# TTGO_shield_revE.net
KiCad netlist of a schematic drawn in EAGLE
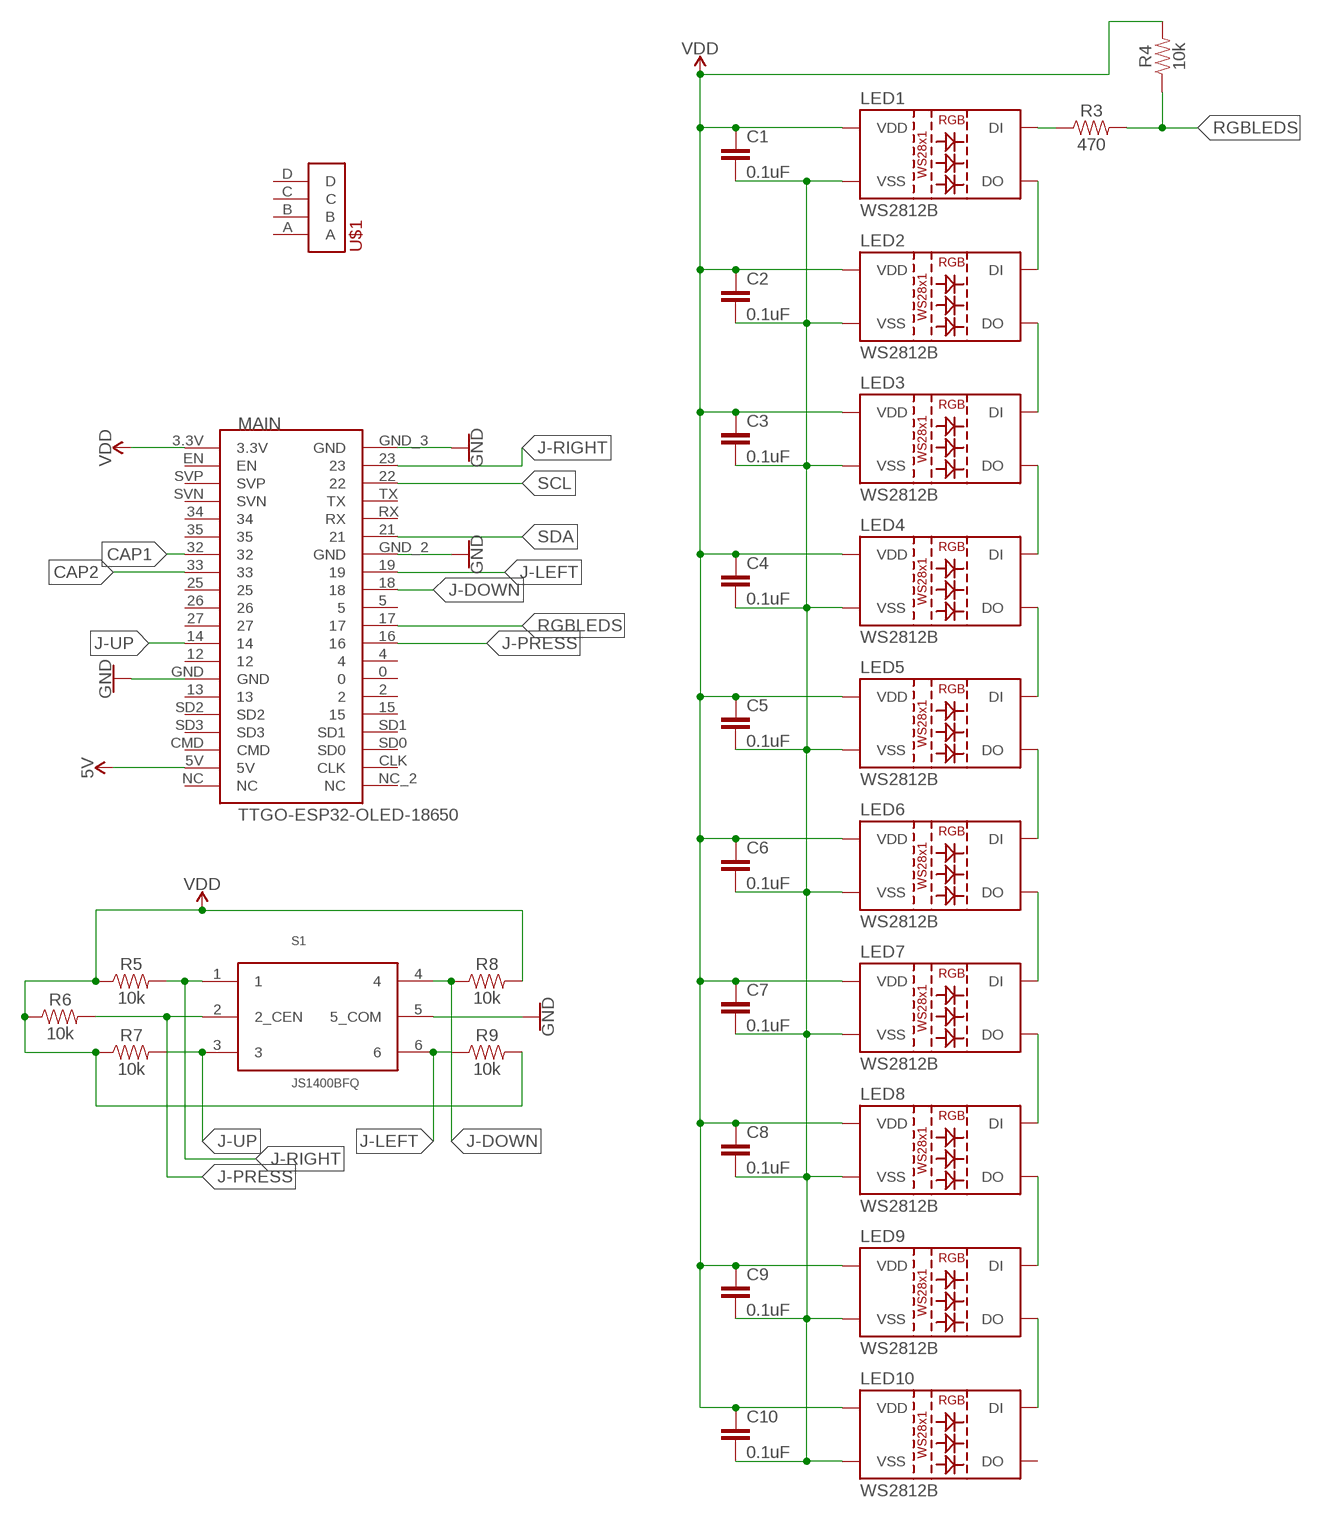
[diagram p0: schematic, sheet 1]

(export (version "E")
  (design (tool "Eeschema 10.0.6"))
  (components
    (comp (ref "C1")
      (value "0.1uF")
      (footprint "eagle-import:0603")
      (libsource (lib "eagle-import") (part "0.1UF-0603-25V-5%"))
    )
    (comp (ref "C2")
      (value "0.1uF")
      (footprint "eagle-import:0603")
      (libsource (lib "eagle-import") (part "0.1UF-0603-25V-5%"))
    )
    (comp (ref "C3")
      (value "0.1uF")
      (footprint "eagle-import:0603")
      (libsource (lib "eagle-import") (part "0.1UF-0603-25V-5%"))
    )
    (comp (ref "C4")
      (value "0.1uF")
      (footprint "eagle-import:0603")
      (libsource (lib "eagle-import") (part "0.1UF-0603-25V-5%"))
    )
    (comp (ref "C5")
      (value "0.1uF")
      (footprint "eagle-import:0603")
      (libsource (lib "eagle-import") (part "0.1UF-0603-25V-5%"))
    )
    (comp (ref "C6")
      (value "0.1uF")
      (footprint "eagle-import:0603")
      (libsource (lib "eagle-import") (part "0.1UF-0603-25V-5%"))
    )
    (comp (ref "C7")
      (value "0.1uF")
      (footprint "eagle-import:0603")
      (libsource (lib "eagle-import") (part "0.1UF-0603-25V-5%"))
    )
    (comp (ref "C8")
      (value "0.1uF")
      (footprint "eagle-import:0603")
      (libsource (lib "eagle-import") (part "0.1UF-0603-25V-5%"))
    )
    (comp (ref "C9")
      (value "0.1uF")
      (footprint "eagle-import:0603")
      (libsource (lib "eagle-import") (part "0.1UF-0603-25V-5%"))
    )
    (comp (ref "C10")
      (value "0.1uF")
      (footprint "eagle-import:0603")
      (libsource (lib "eagle-import") (part "0.1UF-0603-25V-5%"))
    )
    (comp (ref "LED1")
      (value "WS2812B")
      (footprint "eagle-import:WS2812B")
      (libsource (lib "eagle-import") (part "WS2812B"))
    )
    (comp (ref "LED2")
      (value "WS2812B")
      (footprint "eagle-import:WS2812B")
      (libsource (lib "eagle-import") (part "WS2812B"))
    )
    (comp (ref "LED3")
      (value "WS2812B")
      (footprint "eagle-import:WS2812B")
      (libsource (lib "eagle-import") (part "WS2812B"))
    )
    (comp (ref "LED4")
      (value "WS2812B")
      (footprint "eagle-import:WS2812B")
      (libsource (lib "eagle-import") (part "WS2812B"))
    )
    (comp (ref "LED5")
      (value "WS2812B")
      (footprint "eagle-import:WS2812B")
      (libsource (lib "eagle-import") (part "WS2812B"))
    )
    (comp (ref "LED6")
      (value "WS2812B")
      (footprint "eagle-import:WS2812B")
      (libsource (lib "eagle-import") (part "WS2812B"))
    )
    (comp (ref "LED7")
      (value "WS2812B")
      (footprint "eagle-import:WS2812B")
      (libsource (lib "eagle-import") (part "WS2812B"))
    )
    (comp (ref "LED8")
      (value "WS2812B")
      (footprint "eagle-import:WS2812B")
      (libsource (lib "eagle-import") (part "WS2812B"))
    )
    (comp (ref "LED9")
      (value "WS2812B")
      (footprint "eagle-import:WS2812B")
      (libsource (lib "eagle-import") (part "WS2812B"))
    )
    (comp (ref "LED10")
      (value "WS2812B")
      (footprint "eagle-import:WS2812B")
      (libsource (lib "eagle-import") (part "WS2812B"))
    )
    (comp (ref "MAIN")
      (value "TTGO-ESP32-OLED-18650")
      (footprint "eagle-import:TTGO-ESP32-OLED-18650")
      (libsource (lib "eagle-import") (part "TTGO-ESP32-OLED-18650"))
    )
    (comp (ref "R3")
      (value "470")
      (footprint "eagle-import:0603")
      (libsource (lib "eagle-import") (part "470OHM-0603-1/10W-1%"))
    )
    (comp (ref "R4")
      (value "10k")
      (footprint "eagle-import:0603")
      (libsource (lib "eagle-import") (part "10KOHM-0603-1/10W-1%"))
    )
    (comp (ref "R5")
      (value "10k")
      (footprint "eagle-import:0603")
      (libsource (lib "eagle-import") (part "10KOHM-0603-1/10W-1%"))
    )
    (comp (ref "R6")
      (value "10k")
      (footprint "eagle-import:0603")
      (libsource (lib "eagle-import") (part "10KOHM-0603-1/10W-1%"))
    )
    (comp (ref "R7")
      (value "10k")
      (footprint "eagle-import:0603")
      (libsource (lib "eagle-import") (part "10KOHM-0603-1/10W-1%"))
    )
    (comp (ref "R8")
      (value "10k")
      (footprint "eagle-import:0603")
      (libsource (lib "eagle-import") (part "10KOHM-0603-1/10W-1%"))
    )
    (comp (ref "R9")
      (value "10k")
      (footprint "eagle-import:0603")
      (libsource (lib "eagle-import") (part "10KOHM-0603-1/10W-1%"))
    )
    (comp (ref "S1")
      (value "JS1400BFQ")
      (footprint "eagle-import:JS1400BFQ")
      (libsource (lib "eagle-import") (part "JS1400BFQ"))
    )
    (comp (ref "U$1")
      (value "10120045-400LF")
      (footprint "eagle-import:10120045-400LF")
      (libsource (lib "eagle-import") (part "10120045-400LF"))
    )
  )
  (nets
    (net (code "1") (name "5V") (class "Default")
      (node (ref "MAIN") (pin "5V") (pinfunction "5V_5V") (pintype "bidirectional"))
    )
    (net (code "2") (name "CAP1") (class "Default")
      (node (ref "MAIN") (pin "32") (pinfunction "32_32") (pintype "bidirectional"))
    )
    (net (code "3") (name "CAP2") (class "Default")
      (node (ref "MAIN") (pin "33") (pinfunction "33_33") (pintype "bidirectional"))
    )
    (net (code "4") (name "GND") (class "Default")
      (node (ref "MAIN") (pin "GND") (pinfunction "GND_GND") (pintype "bidirectional"))
      (node (ref "MAIN") (pin "GND_2") (pinfunction "GND_GND_2") (pintype "bidirectional"))
      (node (ref "MAIN") (pin "GND_3") (pinfunction "GND_GND_3") (pintype "bidirectional"))
      (node (ref "S1") (pin "5") (pinfunction "5_COM_5") (pintype "bidirectional"))
    )
    (net (code "5") (name "J-DOWN") (class "Default")
      (node (ref "MAIN") (pin "18") (pinfunction "18_18") (pintype "bidirectional"))
      (node (ref "R8") (pin "1") (pinfunction "1_1") (pintype "passive"))
      (node (ref "S1") (pin "4") (pinfunction "4_4") (pintype "bidirectional"))
    )
    (net (code "6") (name "J-LEFT") (class "Default")
      (node (ref "MAIN") (pin "19") (pinfunction "19_19") (pintype "bidirectional"))
      (node (ref "R9") (pin "1") (pinfunction "1_1") (pintype "passive"))
      (node (ref "S1") (pin "6") (pinfunction "6_6") (pintype "bidirectional"))
    )
    (net (code "7") (name "J-PRESS") (class "Default")
      (node (ref "MAIN") (pin "16") (pinfunction "16_16") (pintype "bidirectional"))
      (node (ref "R6") (pin "2") (pinfunction "2_2") (pintype "passive"))
      (node (ref "S1") (pin "2") (pinfunction "2_CEN_2") (pintype "bidirectional"))
    )
    (net (code "8") (name "J-RIGHT") (class "Default")
      (node (ref "MAIN") (pin "23") (pinfunction "23_23") (pintype "bidirectional"))
      (node (ref "R5") (pin "2") (pinfunction "2_2") (pintype "passive"))
      (node (ref "S1") (pin "1") (pinfunction "1_1") (pintype "bidirectional"))
    )
    (net (code "9") (name "J-UP") (class "Default")
      (node (ref "MAIN") (pin "14") (pinfunction "14_14") (pintype "bidirectional"))
      (node (ref "R7") (pin "2") (pinfunction "2_2") (pintype "passive"))
      (node (ref "S1") (pin "3") (pinfunction "3_3") (pintype "bidirectional"))
    )
    (net (code "10") (name "Net-(LED1-DI)") (class "Default")
      (node (ref "LED1") (pin "4") (pinfunction "DI_4") (pintype "bidirectional"))
      (node (ref "R3") (pin "1") (pinfunction "1_1") (pintype "passive"))
    )
    (net (code "11") (name "Net-(LED1-DO)") (class "Default")
      (node (ref "LED1") (pin "2") (pinfunction "DO_2") (pintype "bidirectional"))
      (node (ref "LED2") (pin "4") (pinfunction "DI_4") (pintype "bidirectional"))
    )
    (net (code "12") (name "Net-(LED1-VSS)") (class "Default")
      (node (ref "C1") (pin "2") (pinfunction "2_2") (pintype "passive"))
      (node (ref "C10") (pin "2") (pinfunction "2_2") (pintype "passive"))
      (node (ref "C2") (pin "2") (pinfunction "2_2") (pintype "passive"))
      (node (ref "C3") (pin "2") (pinfunction "2_2") (pintype "passive"))
      (node (ref "C4") (pin "2") (pinfunction "2_2") (pintype "passive"))
      (node (ref "C5") (pin "2") (pinfunction "2_2") (pintype "passive"))
      (node (ref "C6") (pin "2") (pinfunction "2_2") (pintype "passive"))
      (node (ref "C7") (pin "2") (pinfunction "2_2") (pintype "passive"))
      (node (ref "C8") (pin "2") (pinfunction "2_2") (pintype "passive"))
      (node (ref "C9") (pin "2") (pinfunction "2_2") (pintype "passive"))
      (node (ref "LED1") (pin "3") (pinfunction "VSS_3") (pintype "bidirectional"))
      (node (ref "LED10") (pin "3") (pinfunction "VSS_3") (pintype "bidirectional"))
      (node (ref "LED2") (pin "3") (pinfunction "VSS_3") (pintype "bidirectional"))
      (node (ref "LED3") (pin "3") (pinfunction "VSS_3") (pintype "bidirectional"))
      (node (ref "LED4") (pin "3") (pinfunction "VSS_3") (pintype "bidirectional"))
      (node (ref "LED5") (pin "3") (pinfunction "VSS_3") (pintype "bidirectional"))
      (node (ref "LED6") (pin "3") (pinfunction "VSS_3") (pintype "bidirectional"))
      (node (ref "LED7") (pin "3") (pinfunction "VSS_3") (pintype "bidirectional"))
      (node (ref "LED8") (pin "3") (pinfunction "VSS_3") (pintype "bidirectional"))
      (node (ref "LED9") (pin "3") (pinfunction "VSS_3") (pintype "bidirectional"))
    )
    (net (code "13") (name "Net-(LED2-DO)") (class "Default")
      (node (ref "LED2") (pin "2") (pinfunction "DO_2") (pintype "bidirectional"))
      (node (ref "LED3") (pin "4") (pinfunction "DI_4") (pintype "bidirectional"))
    )
    (net (code "14") (name "Net-(LED3-DO)") (class "Default")
      (node (ref "LED3") (pin "2") (pinfunction "DO_2") (pintype "bidirectional"))
      (node (ref "LED4") (pin "4") (pinfunction "DI_4") (pintype "bidirectional"))
    )
    (net (code "15") (name "Net-(LED4-DO)") (class "Default")
      (node (ref "LED4") (pin "2") (pinfunction "DO_2") (pintype "bidirectional"))
      (node (ref "LED5") (pin "4") (pinfunction "DI_4") (pintype "bidirectional"))
    )
    (net (code "16") (name "Net-(LED5-DO)") (class "Default")
      (node (ref "LED5") (pin "2") (pinfunction "DO_2") (pintype "bidirectional"))
      (node (ref "LED6") (pin "4") (pinfunction "DI_4") (pintype "bidirectional"))
    )
    (net (code "17") (name "Net-(LED6-DO)") (class "Default")
      (node (ref "LED6") (pin "2") (pinfunction "DO_2") (pintype "bidirectional"))
      (node (ref "LED7") (pin "4") (pinfunction "DI_4") (pintype "bidirectional"))
    )
    (net (code "18") (name "Net-(LED7-DO)") (class "Default")
      (node (ref "LED7") (pin "2") (pinfunction "DO_2") (pintype "bidirectional"))
      (node (ref "LED8") (pin "4") (pinfunction "DI_4") (pintype "bidirectional"))
    )
    (net (code "19") (name "Net-(LED8-DO)") (class "Default")
      (node (ref "LED8") (pin "2") (pinfunction "DO_2") (pintype "bidirectional"))
      (node (ref "LED9") (pin "4") (pinfunction "DI_4") (pintype "bidirectional"))
    )
    (net (code "20") (name "Net-(LED10-DI)") (class "Default")
      (node (ref "LED10") (pin "4") (pinfunction "DI_4") (pintype "bidirectional"))
      (node (ref "LED9") (pin "2") (pinfunction "DO_2") (pintype "bidirectional"))
    )
    (net (code "21") (name "RGBLEDS") (class "Default")
      (node (ref "MAIN") (pin "17") (pinfunction "17_17") (pintype "bidirectional"))
      (node (ref "R3") (pin "2") (pinfunction "2_2") (pintype "passive"))
      (node (ref "R4") (pin "1") (pinfunction "1_1") (pintype "passive"))
    )
    (net (code "22") (name "SCL") (class "Default")
      (node (ref "MAIN") (pin "22") (pinfunction "22_22") (pintype "bidirectional"))
    )
    (net (code "23") (name "SDA") (class "Default")
      (node (ref "MAIN") (pin "21") (pinfunction "21_21") (pintype "bidirectional"))
    )
    (net (code "24") (name "VDD") (class "Default")
      (node (ref "C1") (pin "1") (pinfunction "1_1") (pintype "passive"))
      (node (ref "C10") (pin "1") (pinfunction "1_1") (pintype "passive"))
      (node (ref "C2") (pin "1") (pinfunction "1_1") (pintype "passive"))
      (node (ref "C3") (pin "1") (pinfunction "1_1") (pintype "passive"))
      (node (ref "C4") (pin "1") (pinfunction "1_1") (pintype "passive"))
      (node (ref "C5") (pin "1") (pinfunction "1_1") (pintype "passive"))
      (node (ref "C6") (pin "1") (pinfunction "1_1") (pintype "passive"))
      (node (ref "C7") (pin "1") (pinfunction "1_1") (pintype "passive"))
      (node (ref "C8") (pin "1") (pinfunction "1_1") (pintype "passive"))
      (node (ref "C9") (pin "1") (pinfunction "1_1") (pintype "passive"))
      (node (ref "LED1") (pin "1") (pinfunction "VDD_1") (pintype "bidirectional"))
      (node (ref "LED10") (pin "1") (pinfunction "VDD_1") (pintype "bidirectional"))
      (node (ref "LED2") (pin "1") (pinfunction "VDD_1") (pintype "bidirectional"))
      (node (ref "LED3") (pin "1") (pinfunction "VDD_1") (pintype "bidirectional"))
      (node (ref "LED4") (pin "1") (pinfunction "VDD_1") (pintype "bidirectional"))
      (node (ref "LED5") (pin "1") (pinfunction "VDD_1") (pintype "bidirectional"))
      (node (ref "LED6") (pin "1") (pinfunction "VDD_1") (pintype "bidirectional"))
      (node (ref "LED7") (pin "1") (pinfunction "VDD_1") (pintype "bidirectional"))
      (node (ref "LED8") (pin "1") (pinfunction "VDD_1") (pintype "bidirectional"))
      (node (ref "LED9") (pin "1") (pinfunction "VDD_1") (pintype "bidirectional"))
      (node (ref "MAIN") (pin "3.3V") (pinfunction "3.3V_3.3V") (pintype "bidirectional"))
      (node (ref "R4") (pin "2") (pinfunction "2_2") (pintype "passive"))
      (node (ref "R5") (pin "1") (pinfunction "1_1") (pintype "passive"))
      (node (ref "R6") (pin "1") (pinfunction "1_1") (pintype "passive"))
      (node (ref "R7") (pin "1") (pinfunction "1_1") (pintype "passive"))
      (node (ref "R8") (pin "2") (pinfunction "2_2") (pintype "passive"))
      (node (ref "R9") (pin "2") (pinfunction "2_2") (pintype "passive"))
    )
    (net (code "25") (name "unconnected-(LED10-DO-Pad2)") (class "Default")
      (node (ref "LED10") (pin "2") (pinfunction "DO_2") (pintype "bidirectional"))
    )
    (net (code "26") (name "unconnected-(MAIN-NC-PadNC_2)") (class "Default")
      (node (ref "MAIN") (pin "NC_2") (pinfunction "NC_NC_2") (pintype "bidirectional"))
    )
    (net (code "27") (name "unconnected-(MAIN-Pad0)") (class "Default")
      (node (ref "MAIN") (pin "0") (pinfunction "0_0") (pintype "bidirectional"))
    )
    (net (code "28") (name "unconnected-(MAIN-Pad2)") (class "Default")
      (node (ref "MAIN") (pin "2") (pinfunction "2_2") (pintype "bidirectional"))
    )
    (net (code "29") (name "unconnected-(MAIN-Pad4)") (class "Default")
      (node (ref "MAIN") (pin "4") (pinfunction "4_4") (pintype "bidirectional"))
    )
    (net (code "30") (name "unconnected-(MAIN-Pad5)") (class "Default")
      (node (ref "MAIN") (pin "5") (pinfunction "5_5") (pintype "bidirectional"))
    )
    (net (code "31") (name "unconnected-(MAIN-Pad12)") (class "Default")
      (node (ref "MAIN") (pin "12") (pinfunction "12_12") (pintype "bidirectional"))
    )
    (net (code "32") (name "unconnected-(MAIN-Pad13)") (class "Default")
      (node (ref "MAIN") (pin "13") (pinfunction "13_13") (pintype "bidirectional"))
    )
    (net (code "33") (name "unconnected-(MAIN-Pad15)") (class "Default")
      (node (ref "MAIN") (pin "15") (pinfunction "15_15") (pintype "bidirectional"))
    )
    (net (code "34") (name "unconnected-(MAIN-Pad25)") (class "Default")
      (node (ref "MAIN") (pin "25") (pinfunction "25_25") (pintype "bidirectional"))
    )
    (net (code "35") (name "unconnected-(MAIN-Pad26)") (class "Default")
      (node (ref "MAIN") (pin "26") (pinfunction "26_26") (pintype "bidirectional"))
    )
    (net (code "36") (name "unconnected-(MAIN-Pad27)") (class "Default")
      (node (ref "MAIN") (pin "27") (pinfunction "27_27") (pintype "bidirectional"))
    )
    (net (code "37") (name "unconnected-(MAIN-Pad34)") (class "Default")
      (node (ref "MAIN") (pin "34") (pinfunction "34_34") (pintype "bidirectional"))
    )
    (net (code "38") (name "unconnected-(MAIN-Pad35)") (class "Default")
      (node (ref "MAIN") (pin "35") (pinfunction "35_35") (pintype "bidirectional"))
    )
    (net (code "39") (name "unconnected-(MAIN-PadCLK)") (class "Default")
      (node (ref "MAIN") (pin "CLK") (pinfunction "CLK_CLK") (pintype "bidirectional"))
    )
    (net (code "40") (name "unconnected-(MAIN-PadCMD)") (class "Default")
      (node (ref "MAIN") (pin "CMD") (pinfunction "CMD_CMD") (pintype "bidirectional"))
    )
    (net (code "41") (name "unconnected-(MAIN-PadEN)") (class "Default")
      (node (ref "MAIN") (pin "EN") (pinfunction "EN_EN") (pintype "bidirectional"))
    )
    (net (code "42") (name "unconnected-(MAIN-PadNC)") (class "Default")
      (node (ref "MAIN") (pin "NC") (pinfunction "NC_NC") (pintype "bidirectional"))
    )
    (net (code "43") (name "unconnected-(MAIN-PadRX)") (class "Default")
      (node (ref "MAIN") (pin "RX") (pinfunction "RX_RX") (pintype "bidirectional"))
    )
    (net (code "44") (name "unconnected-(MAIN-PadSD0)") (class "Default")
      (node (ref "MAIN") (pin "SD0") (pinfunction "SD0_SD0") (pintype "bidirectional"))
    )
    (net (code "45") (name "unconnected-(MAIN-PadSD1)") (class "Default")
      (node (ref "MAIN") (pin "SD1") (pinfunction "SD1_SD1") (pintype "bidirectional"))
    )
    (net (code "46") (name "unconnected-(MAIN-PadSD2)") (class "Default")
      (node (ref "MAIN") (pin "SD2") (pinfunction "SD2_SD2") (pintype "bidirectional"))
    )
    (net (code "47") (name "unconnected-(MAIN-PadSD3)") (class "Default")
      (node (ref "MAIN") (pin "SD3") (pinfunction "SD3_SD3") (pintype "bidirectional"))
    )
    (net (code "48") (name "unconnected-(MAIN-PadSVN)") (class "Default")
      (node (ref "MAIN") (pin "SVN") (pinfunction "SVN_SVN") (pintype "bidirectional"))
    )
    (net (code "49") (name "unconnected-(MAIN-PadSVP)") (class "Default")
      (node (ref "MAIN") (pin "SVP") (pinfunction "SVP_SVP") (pintype "bidirectional"))
    )
    (net (code "50") (name "unconnected-(MAIN-PadTX)") (class "Default")
      (node (ref "MAIN") (pin "TX") (pinfunction "TX_TX") (pintype "bidirectional"))
    )
    (net (code "51") (name "unconnected-(U$1-PadA)") (class "Default")
      (node (ref "U$1") (pin "A") (pinfunction "A_A") (pintype "bidirectional"))
    )
    (net (code "52") (name "unconnected-(U$1-PadB)") (class "Default")
      (node (ref "U$1") (pin "B") (pinfunction "B_B") (pintype "bidirectional"))
    )
    (net (code "53") (name "unconnected-(U$1-PadC)") (class "Default")
      (node (ref "U$1") (pin "C") (pinfunction "C_C") (pintype "bidirectional"))
    )
    (net (code "54") (name "unconnected-(U$1-PadD)") (class "Default")
      (node (ref "U$1") (pin "D") (pinfunction "D_D") (pintype "bidirectional"))
    )
  )
)
